# ATMEGA8_S52.net
KiCad netlist of a schematic drawn in Altium Designer
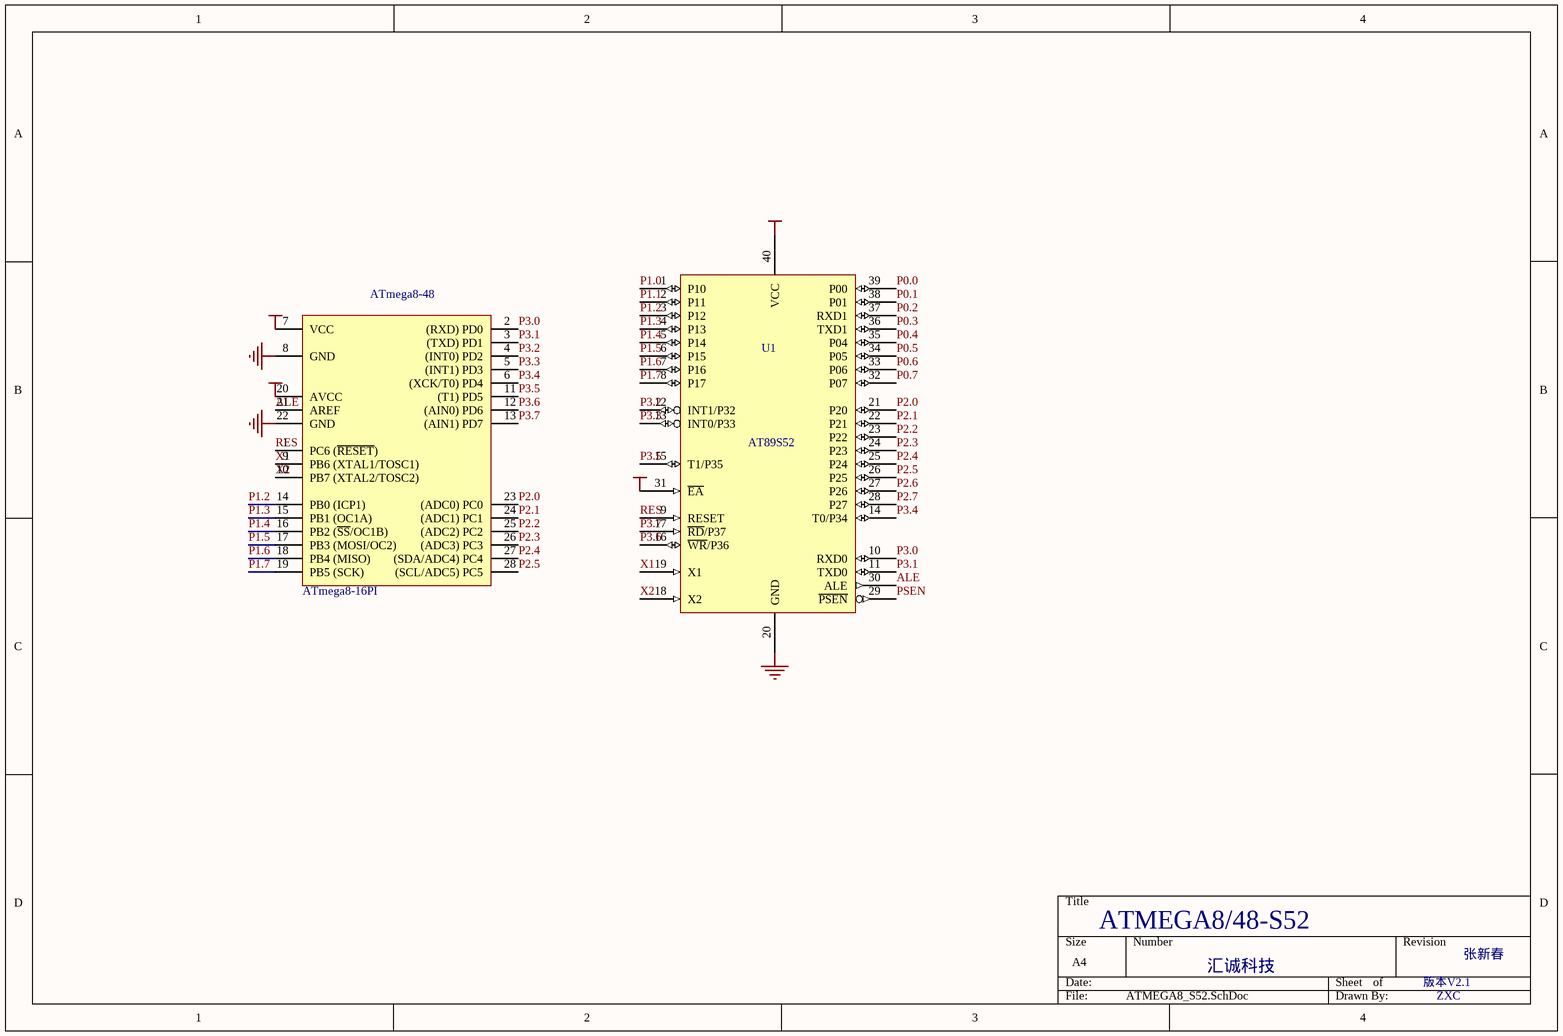
[diagram p0: ATMEGA8_S52.SchDoc]

(export (version "E")
  (design (tool "Eeschema 10.0.6"))
  (components
    (comp (ref "ATmega8-48")
      (value "ATmega8-16PI")
      (footprint "底座DIP-28/引脚7.62mm")
      (description "8 位微处理器/28引脚")
      (fields (field (name "发布者") "磊元工作室"))
      (libsource (lib "微控制处理器") (part "ATmega8-P"))
    )
    (comp (ref "U1") (value "AT89S52") (footprint "DIP-40") (libsource (lib "OldCow1 (2)") (part "8051")))
  )
  (nets
    (net (code "1") (name "/ALE") (class "Default")
      (node (ref "ATmega8-48") (pin "21") (pinfunction "AREF_21") (pintype "passive"))
      (node (ref "U1") (pin "30") (pinfunction "ALE_30") (pintype "output"))
    )
    (net (code "2") (name "/P0.0") (class "Default")
      (node (ref "U1") (pin "39") (pinfunction "P00_39") (pintype "bidirectional"))
    )
    (net (code "3") (name "/P0.1") (class "Default")
      (node (ref "U1") (pin "38") (pinfunction "P01_38") (pintype "bidirectional"))
    )
    (net (code "4") (name "/P0.2") (class "Default")
      (node (ref "U1") (pin "37") (pinfunction "RXD1_37") (pintype "bidirectional"))
    )
    (net (code "5") (name "/P0.3") (class "Default")
      (node (ref "U1") (pin "36") (pinfunction "TXD1_36") (pintype "bidirectional"))
    )
    (net (code "6") (name "/P0.4") (class "Default")
      (node (ref "U1") (pin "35") (pinfunction "P04_35") (pintype "bidirectional"))
    )
    (net (code "7") (name "/P0.5") (class "Default")
      (node (ref "U1") (pin "34") (pinfunction "P05_34") (pintype "bidirectional"))
    )
    (net (code "8") (name "/P0.6") (class "Default")
      (node (ref "U1") (pin "33") (pinfunction "P06_33") (pintype "bidirectional"))
    )
    (net (code "9") (name "/P0.7") (class "Default")
      (node (ref "U1") (pin "32") (pinfunction "P07_32") (pintype "bidirectional"))
    )
    (net (code "10") (name "/P1.0") (class "Default")
      (node (ref "U1") (pin "1") (pinfunction "P10_1") (pintype "bidirectional"))
    )
    (net (code "11") (name "/P1.1") (class "Default")
      (node (ref "U1") (pin "2") (pinfunction "P11_2") (pintype "bidirectional"))
    )
    (net (code "12") (name "/P1.2") (class "Default")
      (node (ref "ATmega8-48") (pin "14") (pinfunction "PB0_(ICP1)_14") (pintype "passive"))
      (node (ref "U1") (pin "3") (pinfunction "P12_3") (pintype "bidirectional"))
    )
    (net (code "13") (name "/P1.3") (class "Default")
      (node (ref "ATmega8-48") (pin "15") (pinfunction "PB1_(OC1A)_15") (pintype "passive"))
      (node (ref "U1") (pin "4") (pinfunction "P13_4") (pintype "bidirectional"))
    )
    (net (code "14") (name "/P1.4") (class "Default")
      (node (ref "ATmega8-48") (pin "16") (pinfunction "PB2_(~{SS}/OC1B)_16") (pintype "passive"))
      (node (ref "U1") (pin "5") (pinfunction "P14_5") (pintype "bidirectional"))
    )
    (net (code "15") (name "/P1.5") (class "Default")
      (node (ref "ATmega8-48") (pin "17") (pinfunction "PB3_(MOSI/OC2)_17") (pintype "passive"))
      (node (ref "U1") (pin "6") (pinfunction "P15_6") (pintype "bidirectional"))
    )
    (net (code "16") (name "/P1.6") (class "Default")
      (node (ref "ATmega8-48") (pin "18") (pinfunction "PB4_(MISO)_18") (pintype "passive"))
      (node (ref "U1") (pin "7") (pinfunction "P16_7") (pintype "bidirectional"))
    )
    (net (code "17") (name "/P1.7") (class "Default")
      (node (ref "ATmega8-48") (pin "19") (pinfunction "PB5_(SCK)_19") (pintype "passive"))
      (node (ref "U1") (pin "8") (pinfunction "P17_8") (pintype "bidirectional"))
    )
    (net (code "18") (name "/P2.0") (class "Default")
      (node (ref "ATmega8-48") (pin "23") (pinfunction "(ADC0)_PC0_23") (pintype "passive"))
      (node (ref "U1") (pin "21") (pinfunction "P20_21") (pintype "bidirectional"))
    )
    (net (code "19") (name "/P2.1") (class "Default")
      (node (ref "ATmega8-48") (pin "24") (pinfunction "(ADC1)_PC1_24") (pintype "passive"))
      (node (ref "U1") (pin "22") (pinfunction "P21_22") (pintype "bidirectional"))
    )
    (net (code "20") (name "/P2.2") (class "Default")
      (node (ref "ATmega8-48") (pin "25") (pinfunction "(ADC2)_PC2_25") (pintype "passive"))
      (node (ref "U1") (pin "23") (pinfunction "P22_23") (pintype "bidirectional"))
    )
    (net (code "21") (name "/P2.3") (class "Default")
      (node (ref "ATmega8-48") (pin "26") (pinfunction "(ADC3)_PC3_26") (pintype "passive"))
      (node (ref "U1") (pin "24") (pinfunction "P23_24") (pintype "bidirectional"))
    )
    (net (code "22") (name "/P2.4") (class "Default")
      (node (ref "ATmega8-48") (pin "27") (pinfunction "(SDA/ADC4)_PC4_27") (pintype "passive"))
      (node (ref "U1") (pin "25") (pinfunction "P24_25") (pintype "bidirectional"))
    )
    (net (code "23") (name "/P2.5") (class "Default")
      (node (ref "ATmega8-48") (pin "28") (pinfunction "(SCL/ADC5)_PC5_28") (pintype "passive"))
      (node (ref "U1") (pin "26") (pinfunction "P25_26") (pintype "bidirectional"))
    )
    (net (code "24") (name "/P2.6") (class "Default")
      (node (ref "U1") (pin "27") (pinfunction "P26_27") (pintype "bidirectional"))
    )
    (net (code "25") (name "/P2.7") (class "Default")
      (node (ref "U1") (pin "28") (pinfunction "P27_28") (pintype "bidirectional"))
    )
    (net (code "26") (name "/P3.0") (class "Default")
      (node (ref "ATmega8-48") (pin "2") (pinfunction "(RXD)_PD0_2") (pintype "passive"))
      (node (ref "U1") (pin "10") (pinfunction "RXD0_10") (pintype "bidirectional"))
    )
    (net (code "27") (name "/P3.1") (class "Default")
      (node (ref "ATmega8-48") (pin "3") (pinfunction "(TXD)_PD1_3") (pintype "passive"))
      (node (ref "U1") (pin "11") (pinfunction "TXD0_11") (pintype "bidirectional"))
    )
    (net (code "28") (name "/P3.2") (class "Default")
      (node (ref "ATmega8-48") (pin "4") (pinfunction "(INT0)_PD2_4") (pintype "passive"))
      (node (ref "U1") (pin "12") (pinfunction "INT1/P32_12") (pintype "bidirectional"))
    )
    (net (code "29") (name "/P3.3") (class "Default")
      (node (ref "ATmega8-48") (pin "5") (pinfunction "(INT1)_PD3_5") (pintype "passive"))
      (node (ref "U1") (pin "13") (pinfunction "INT0/P33_13") (pintype "bidirectional"))
    )
    (net (code "30") (name "/P3.4") (class "Default")
      (node (ref "ATmega8-48") (pin "6") (pinfunction "(XCK/T0)_PD4_6") (pintype "passive"))
      (node (ref "U1") (pin "14") (pinfunction "T0/P34_14") (pintype "bidirectional"))
    )
    (net (code "31") (name "/P3.5") (class "Default")
      (node (ref "ATmega8-48") (pin "11") (pinfunction "(T1)_PD5_11") (pintype "passive"))
      (node (ref "U1") (pin "15") (pinfunction "T1/P35_15") (pintype "bidirectional"))
    )
    (net (code "32") (name "/P3.6") (class "Default")
      (node (ref "ATmega8-48") (pin "12") (pinfunction "(AIN0)_PD6_12") (pintype "passive"))
      (node (ref "U1") (pin "16") (pinfunction "~{WR}/P36_16") (pintype "bidirectional"))
    )
    (net (code "33") (name "/P3.7") (class "Default")
      (node (ref "ATmega8-48") (pin "13") (pinfunction "(AIN1)_PD7_13") (pintype "passive"))
      (node (ref "U1") (pin "17") (pinfunction "~{RD}/P37_17") (pintype "input"))
    )
    (net (code "34") (name "/PSEN") (class "Default")
      (node (ref "U1") (pin "29") (pinfunction "~{PSEN}_29") (pintype "output"))
    )
    (net (code "35") (name "/RES") (class "Default")
      (node (ref "ATmega8-48") (pin "1") (pinfunction "PC6_(~{RESET})_1") (pintype "passive"))
      (node (ref "U1") (pin "9") (pinfunction "RESET_9") (pintype "input"))
    )
    (net (code "36") (name "/X1") (class "Default")
      (node (ref "ATmega8-48") (pin "9") (pinfunction "PB6_(XTAL1/TOSC1)_9") (pintype "passive"))
      (node (ref "U1") (pin "19") (pinfunction "X1_19") (pintype "input"))
    )
    (net (code "37") (name "/X2") (class "Default")
      (node (ref "ATmega8-48") (pin "10") (pinfunction "PB7_(XTAL2/TOSC2)_10") (pintype "passive"))
      (node (ref "U1") (pin "18") (pinfunction "X2_18") (pintype "input"))
    )
    (net (code "38") (name "GND") (class "Default")
      (node (ref "ATmega8-48") (pin "22") (pinfunction "GND_22") (pintype "passive"))
      (node (ref "ATmega8-48") (pin "8") (pinfunction "GND_8") (pintype "passive"))
      (node (ref "U1") (pin "20") (pinfunction "GND_20") (pintype "power_in"))
    )
    (net (code "39") (name "VCC") (class "Default")
      (node (ref "ATmega8-48") (pin "20") (pinfunction "AVCC_20") (pintype "passive"))
      (node (ref "ATmega8-48") (pin "7") (pinfunction "VCC_7") (pintype "passive"))
      (node (ref "U1") (pin "31") (pinfunction "~{EA}_31") (pintype "input"))
      (node (ref "U1") (pin "40") (pinfunction "VCC_40") (pintype "power_in"))
    )
  )
)
